# transponder.net
KiCad netlist of a schematic drawn in EAGLE
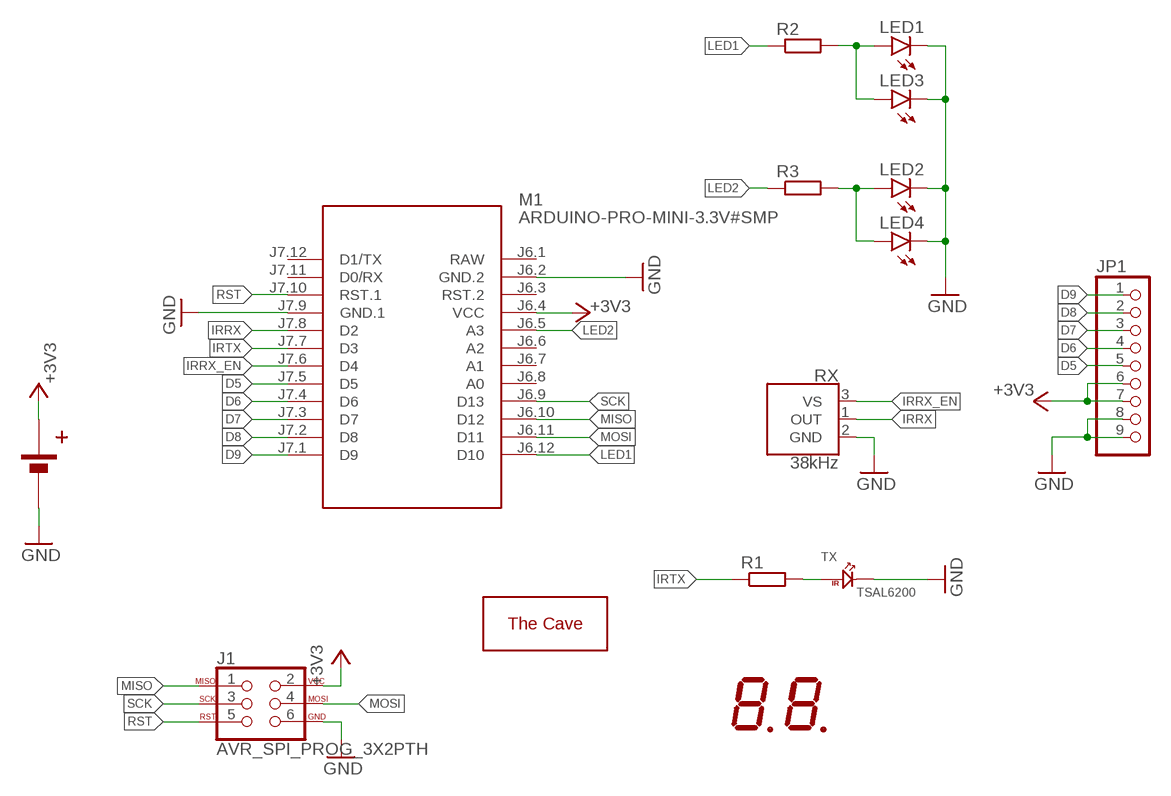
[diagram p0: schematic, sheet 1]

(export (version "E")
  (design (tool "Eeschema 10.0.6"))
  (components
    (comp (ref "BAT1")
      (value "BH-321-2P")
      (footprint "eagle-import:2AA_BATTERY")
      (libsource (lib "eagle-import") (part "BH-321-2P"))
    )
    (comp (ref "J1")
      (value "AVR_SPI_PROG_3X2PTH")
      (footprint "eagle-import:2X3")
      (libsource (lib "eagle-import") (part "AVR_SPI_PROG_3X2PTH"))
    )
    (comp (ref "JP1")
      (value "PINHD-1X9")
      (footprint "eagle-import:1X09")
      (libsource (lib "eagle-import") (part "PINHD-1X9"))
    )
    (comp (ref "LED1")
      (value "LED5MM")
      (footprint "eagle-import:LED5MM")
      (libsource (lib "eagle-import") (part "LED5MM"))
    )
    (comp (ref "LED2")
      (value "LED5MM")
      (footprint "eagle-import:LED5MM")
      (libsource (lib "eagle-import") (part "LED5MM"))
    )
    (comp (ref "LED3")
      (value "LEDCHIPLED_1206")
      (footprint "eagle-import:CHIPLED_1206")
      (libsource (lib "eagle-import") (part "LEDCHIPLED_1206"))
    )
    (comp (ref "LED4")
      (value "LEDCHIPLED_1206")
      (footprint "eagle-import:CHIPLED_1206")
      (libsource (lib "eagle-import") (part "LEDCHIPLED_1206"))
    )
    (comp (ref "LED5")
      (value "LCD_DIGIT")
      (footprint "eagle-import:LCD_DIGIT")
      (libsource (lib "eagle-import") (part "LCD_DIGIT"))
    )
    (comp (ref "LED6")
      (value "LCD_DIGIT")
      (footprint "eagle-import:LCD_DIGIT")
      (libsource (lib "eagle-import") (part "LCD_DIGIT"))
    )
    (comp (ref "M1")
      (value "ARDUINO-PRO-MINI-3.3V#SMP")
      (footprint "eagle-import:ARDUINO-PRO-MINI#SMP")
      (libsource (lib "eagle-import") (part "ARDUINO-PRO-MINI-#SMP3.3V"))
    )
    (comp (ref "R1")
      (value "R-EU_R0805")
      (footprint "eagle-import:R0805")
      (libsource (lib "eagle-import") (part "R-EU_R0805"))
    )
    (comp (ref "R2")
      (value "R-EU_R0805")
      (footprint "eagle-import:R0805")
      (libsource (lib "eagle-import") (part "R-EU_R0805"))
    )
    (comp (ref "R3")
      (value "R-EU_R0805")
      (footprint "eagle-import:R0805")
      (libsource (lib "eagle-import") (part "R-EU_R0805"))
    )
    (comp (ref "RX")
      (value "38kHz")
      (footprint "eagle-import:TSOP382")
      (libsource (lib "eagle-import") (part "TSOP38238"))
    )
    (comp (ref "TX")
      (value "TSAL6200")
      (footprint "eagle-import:TSAL6200")
      (libsource (lib "eagle-import") (part "TSAL6200"))
    )
    (comp (ref "U$1")
      (value "THECAVE_LOGO_NEW_TOP_SMALL")
      (footprint "eagle-import:NEW_LOGO_SMALL_TOP")
      (libsource (lib "eagle-import") (part "THECAVE_LOGO_NEW_TOP_SMALL"))
    )
  )
  (nets
    (net (code "1") (name "+3V3") (class "Default")
      (node (ref "BAT1") (pin "P$1") (pinfunction "VCC_P$1") (pintype "power_in"))
      (node (ref "J1") (pin "2") (pinfunction "2_2") (pintype "passive"))
      (node (ref "JP1") (pin "6") (pinfunction "6_6") (pintype "passive"))
      (node (ref "JP1") (pin "7") (pinfunction "7_7") (pintype "passive"))
      (node (ref "M1") (pin "J6.4") (pinfunction "VCC_J6.4") (pintype "power_in"))
    )
    (net (code "2") (name "/RAW") (class "Default")
      (node (ref "M1") (pin "J6.1") (pinfunction "RAW_J6.1") (pintype "power_in"))
    )
    (net (code "3") (name "D5") (class "Default")
      (node (ref "JP1") (pin "5") (pinfunction "5_5") (pintype "passive"))
      (node (ref "M1") (pin "J7.5") (pinfunction "D5_J7.5") (pintype "bidirectional"))
    )
    (net (code "4") (name "D6") (class "Default")
      (node (ref "JP1") (pin "4") (pinfunction "4_4") (pintype "passive"))
      (node (ref "M1") (pin "J7.4") (pinfunction "D6_J7.4") (pintype "bidirectional"))
    )
    (net (code "5") (name "D7") (class "Default")
      (node (ref "JP1") (pin "3") (pinfunction "3_3") (pintype "passive"))
      (node (ref "M1") (pin "J7.3") (pinfunction "D7_J7.3") (pintype "bidirectional"))
    )
    (net (code "6") (name "D8") (class "Default")
      (node (ref "JP1") (pin "2") (pinfunction "2_2") (pintype "passive"))
      (node (ref "M1") (pin "J7.2") (pinfunction "D8_J7.2") (pintype "bidirectional"))
    )
    (net (code "7") (name "D9") (class "Default")
      (node (ref "JP1") (pin "1") (pinfunction "1_1") (pintype "passive"))
      (node (ref "M1") (pin "J7.1") (pinfunction "D9_J7.1") (pintype "bidirectional"))
    )
    (net (code "8") (name "GND") (class "Default")
      (node (ref "BAT1") (pin "P$2") (pinfunction "GND_P$2") (pintype "power_in"))
      (node (ref "J1") (pin "6") (pinfunction "6_6") (pintype "passive"))
      (node (ref "JP1") (pin "8") (pinfunction "8_8") (pintype "passive"))
      (node (ref "JP1") (pin "9") (pinfunction "9_9") (pintype "passive"))
      (node (ref "LED1") (pin "K") (pinfunction "C_K") (pintype "passive"))
      (node (ref "LED2") (pin "K") (pinfunction "C_K") (pintype "passive"))
      (node (ref "LED3") (pin "C") (pinfunction "C_C") (pintype "passive"))
      (node (ref "LED4") (pin "C") (pinfunction "C_C") (pintype "passive"))
      (node (ref "M1") (pin "J6.2") (pinfunction "GND.2_J6.2") (pintype "power_in"))
      (node (ref "M1") (pin "J7.9") (pinfunction "GND.1_J7.9") (pintype "power_in"))
      (node (ref "RX") (pin "2") (pinfunction "GND_2") (pintype "bidirectional"))
      (node (ref "TX") (pin "N") (pinfunction "N_N") (pintype "bidirectional"))
    )
    (net (code "9") (name "IRRX") (class "Default")
      (node (ref "M1") (pin "J7.8") (pinfunction "D2_J7.8") (pintype "bidirectional"))
      (node (ref "RX") (pin "1") (pinfunction "OUT_1") (pintype "bidirectional"))
    )
    (net (code "10") (name "IRRX_EN") (class "Default")
      (node (ref "M1") (pin "J7.6") (pinfunction "D4_J7.6") (pintype "bidirectional"))
      (node (ref "RX") (pin "3") (pinfunction "VS_3") (pintype "bidirectional"))
    )
    (net (code "11") (name "IRTX") (class "Default")
      (node (ref "M1") (pin "J7.7") (pinfunction "D3_J7.7") (pintype "bidirectional"))
      (node (ref "R1") (pin "1") (pinfunction "1_1") (pintype "passive"))
    )
    (net (code "12") (name "LED1") (class "Default")
      (node (ref "M1") (pin "J6.12") (pinfunction "D10_J6.12") (pintype "bidirectional"))
      (node (ref "R2") (pin "1") (pinfunction "1_1") (pintype "passive"))
    )
    (net (code "13") (name "LED2") (class "Default")
      (node (ref "M1") (pin "J6.5") (pinfunction "A3_J6.5") (pintype "bidirectional"))
      (node (ref "R3") (pin "1") (pinfunction "1_1") (pintype "passive"))
    )
    (net (code "14") (name "MISO") (class "Default")
      (node (ref "J1") (pin "1") (pinfunction "1_1") (pintype "passive"))
      (node (ref "M1") (pin "J6.10") (pinfunction "D12_J6.10") (pintype "bidirectional"))
    )
    (net (code "15") (name "MOSI") (class "Default")
      (node (ref "J1") (pin "4") (pinfunction "4_4") (pintype "passive"))
      (node (ref "M1") (pin "J6.11") (pinfunction "D11_J6.11") (pintype "bidirectional"))
    )
    (net (code "16") (name "Net-(LED1-PadA)") (class "Default")
      (node (ref "LED1") (pin "A") (pinfunction "A_A") (pintype "passive"))
      (node (ref "LED3") (pin "A") (pinfunction "A_A") (pintype "passive"))
      (node (ref "R2") (pin "2") (pinfunction "2_2") (pintype "passive"))
    )
    (net (code "17") (name "Net-(LED2-PadA)") (class "Default")
      (node (ref "LED2") (pin "A") (pinfunction "A_A") (pintype "passive"))
      (node (ref "LED4") (pin "A") (pinfunction "A_A") (pintype "passive"))
      (node (ref "R3") (pin "2") (pinfunction "2_2") (pintype "passive"))
    )
    (net (code "18") (name "Net-(R1-Pad2)") (class "Default")
      (node (ref "R1") (pin "2") (pinfunction "2_2") (pintype "passive"))
      (node (ref "TX") (pin "P") (pinfunction "P_P") (pintype "bidirectional"))
    )
    (net (code "19") (name "RST") (class "Default")
      (node (ref "J1") (pin "5") (pinfunction "5_5") (pintype "passive"))
      (node (ref "M1") (pin "J7.10") (pinfunction "RST.1_J7.10") (pintype "bidirectional"))
    )
    (net (code "20") (name "SCK") (class "Default")
      (node (ref "J1") (pin "3") (pinfunction "3_3") (pintype "passive"))
      (node (ref "M1") (pin "J6.9") (pinfunction "D13_J6.9") (pintype "bidirectional"))
    )
    (net (code "21") (name "unconnected-(M1-A0-PadJ6.8)") (class "Default")
      (node (ref "M1") (pin "J6.8") (pinfunction "A0_J6.8") (pintype "bidirectional"))
    )
    (net (code "22") (name "unconnected-(M1-A1-PadJ6.7)") (class "Default")
      (node (ref "M1") (pin "J6.7") (pinfunction "A1_J6.7") (pintype "bidirectional"))
    )
    (net (code "23") (name "unconnected-(M1-A2-PadJ6.6)") (class "Default")
      (node (ref "M1") (pin "J6.6") (pinfunction "A2_J6.6") (pintype "bidirectional"))
    )
    (net (code "24") (name "unconnected-(M1-D0{slash}RX-PadJ7.11)") (class "Default")
      (node (ref "M1") (pin "J7.11") (pinfunction "D0/RX_J7.11") (pintype "bidirectional"))
    )
    (net (code "25") (name "unconnected-(M1-D1{slash}TX-PadJ7.12)") (class "Default")
      (node (ref "M1") (pin "J7.12") (pinfunction "D1/TX_J7.12") (pintype "bidirectional"))
    )
    (net (code "26") (name "unconnected-(M1-RST.2-PadJ6.3)") (class "Default")
      (node (ref "M1") (pin "J6.3") (pinfunction "RST.2_J6.3") (pintype "bidirectional"))
    )
  )
)
